# level_shifter.net
KiCad netlist of a schematic drawn in Altium Designer
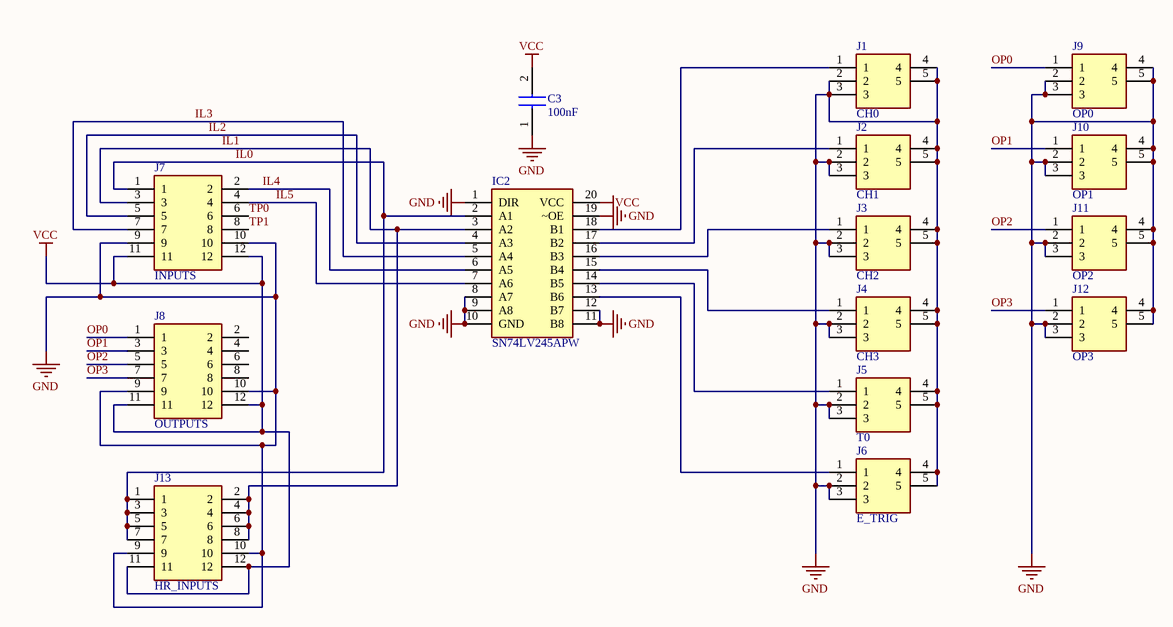
[diagram p0: level_shifter.SchDoc]

(export (version "E")
  (design (tool "Eeschema 10.0.6"))
  (components
    (comp (ref "C3")
      (value "100nF")
      (footprint "SamacSys:CAPC1005X56N")
      (description "Capacitor")
      (fields
        (field (name "MANUFACTURER_PART_NUMBER") "0402YC104MAT2A")
        (field (name "MOUSER PART NUMBER") "581-0402YC104MAT2A")
      )
      (libsource (lib "*") (part "0402YC104MAT2A"))
    )
    (comp (ref "IC2")
      (value "SN74LV245APW")
      (footprint "SamacSys:SOP65P640X120-20N")
      (description "Integrated Circuit")
      (fields
        (field (name "MOUSER PART NUMBER") "595-SN74LV245APW")
        (field (name "RS PART NUMBER") "4394371")
      )
      (libsource (lib "*") (part "SN74LV245APW"))
    )
    (comp (ref "J1")
      (value "CH0")
      (footprint "SamacSys:142-0701-501")
      (description "Connector")
      (fields
        (field (name "RS PART NUMBER") "8859850")
        (field (name "MANUFACTURER_PART_NUMBER") "142-0701-501")
      )
      (libsource (lib "*") (part "142-0701-501"))
    )
    (comp (ref "J2")
      (value "CH1")
      (footprint "SamacSys:142-0701-501")
      (description "Connector")
      (fields
        (field (name "RS PART NUMBER") "8859850")
        (field (name "MANUFACTURER_PART_NUMBER") "142-0701-501")
      )
      (libsource (lib "*") (part "142-0701-501"))
    )
    (comp (ref "J3")
      (value "CH2")
      (footprint "SamacSys:142-0701-501")
      (description "Connector")
      (fields
        (field (name "RS PART NUMBER") "8859850")
        (field (name "MANUFACTURER_PART_NUMBER") "142-0701-501")
      )
      (libsource (lib "*") (part "142-0701-501"))
    )
    (comp (ref "J4")
      (value "CH3")
      (footprint "SamacSys:142-0701-501")
      (description "Connector")
      (fields
        (field (name "RS PART NUMBER") "8859850")
        (field (name "MANUFACTURER_PART_NUMBER") "142-0701-501")
      )
      (libsource (lib "*") (part "142-0701-501"))
    )
    (comp (ref "J5")
      (value "T0")
      (footprint "SamacSys:142-0701-501")
      (description "Connector")
      (fields
        (field (name "RS PART NUMBER") "8859850")
        (field (name "MANUFACTURER_PART_NUMBER") "142-0701-501")
      )
      (libsource (lib "*") (part "142-0701-501"))
    )
    (comp (ref "J6")
      (value "E_TRIG")
      (footprint "SamacSys:142-0701-501")
      (description "Connector")
      (fields
        (field (name "RS PART NUMBER") "8859850")
        (field (name "MANUFACTURER_PART_NUMBER") "142-0701-501")
      )
      (libsource (lib "*") (part "142-0701-501"))
    )
    (comp (ref "J7")
      (value "INPUTS")
      (footprint "SamacSys:HDRRA12W64P254_2X6_1524X254X610P")
      (description "Connector")
      (fields
        (field (name "MANUFACTURER_PART_NUMBER") "TSW-106-08-L-D-RA")
        (field (name "MOUSER PART NUMBER") "200-TSW10608LDRA")
      )
      (libsource (lib "*") (part "TSW-106-08-L-D-RA"))
    )
    (comp (ref "J8")
      (value "OUTPUTS")
      (footprint "SamacSys:HDRRA12W64P254_2X6_1524X254X610P")
      (description "Connector")
      (fields
        (field (name "MANUFACTURER_PART_NUMBER") "TSW-106-08-L-D-RA")
        (field (name "MOUSER PART NUMBER") "200-TSW10608LDRA")
      )
      (libsource (lib "*") (part "TSW-106-08-L-D-RA"))
    )
    (comp (ref "J9")
      (value "OP0")
      (footprint "SamacSys:142-0701-501")
      (description "Connector")
      (fields
        (field (name "RS PART NUMBER") "8859850")
        (field (name "MANUFACTURER_PART_NUMBER") "142-0701-501")
      )
      (libsource (lib "*") (part "142-0701-501"))
    )
    (comp (ref "J10")
      (value "OP1")
      (footprint "SamacSys:142-0701-501")
      (description "Connector")
      (fields
        (field (name "RS PART NUMBER") "8859850")
        (field (name "MANUFACTURER_PART_NUMBER") "142-0701-501")
      )
      (libsource (lib "*") (part "142-0701-501"))
    )
    (comp (ref "J11")
      (value "OP2")
      (footprint "SamacSys:142-0701-501")
      (description "Connector")
      (fields
        (field (name "RS PART NUMBER") "8859850")
        (field (name "MANUFACTURER_PART_NUMBER") "142-0701-501")
      )
      (libsource (lib "*") (part "142-0701-501"))
    )
    (comp (ref "J12")
      (value "OP3")
      (footprint "SamacSys:142-0701-501")
      (description "Connector")
      (fields
        (field (name "RS PART NUMBER") "8859850")
        (field (name "MANUFACTURER_PART_NUMBER") "142-0701-501")
      )
      (libsource (lib "*") (part "142-0701-501"))
    )
    (comp (ref "J13")
      (value "HR_INPUTS")
      (footprint "SamacSys:HDRRA12W64P254_2X6_1524X254X610P")
      (description "Connector")
      (fields
        (field (name "MANUFACTURER_PART_NUMBER") "TSW-106-08-L-D-RA")
        (field (name "MOUSER PART NUMBER") "200-TSW10608LDRA")
      )
      (libsource (lib "*") (part "TSW-106-08-L-D-RA"))
    )
  )
  (nets
    (net (code "1") (name "/IL0") (class "Default")
      (node (ref "IC2") (pin "2") (pinfunction "A1_2") (pintype "passive"))
      (node (ref "J13") (pin "1") (pinfunction "1_1") (pintype "passive"))
      (node (ref "J13") (pin "3") (pinfunction "3_3") (pintype "passive"))
      (node (ref "J13") (pin "5") (pinfunction "5_5") (pintype "passive"))
      (node (ref "J13") (pin "7") (pinfunction "7_7") (pintype "passive"))
      (node (ref "J7") (pin "1") (pinfunction "1_1") (pintype "passive"))
    )
    (net (code "2") (name "/IL1") (class "Default")
      (node (ref "IC2") (pin "3") (pinfunction "A2_3") (pintype "passive"))
      (node (ref "J13") (pin "2") (pinfunction "2_2") (pintype "passive"))
      (node (ref "J13") (pin "4") (pinfunction "4_4") (pintype "passive"))
      (node (ref "J13") (pin "6") (pinfunction "6_6") (pintype "passive"))
      (node (ref "J13") (pin "8") (pinfunction "8_8") (pintype "passive"))
      (node (ref "J7") (pin "3") (pinfunction "3_3") (pintype "passive"))
    )
    (net (code "3") (name "/IL2") (class "Default")
      (node (ref "IC2") (pin "4") (pinfunction "A3_4") (pintype "passive"))
      (node (ref "J7") (pin "5") (pinfunction "5_5") (pintype "passive"))
    )
    (net (code "4") (name "/IL3") (class "Default")
      (node (ref "IC2") (pin "5") (pinfunction "A4_5") (pintype "passive"))
      (node (ref "J7") (pin "7") (pinfunction "7_7") (pintype "passive"))
    )
    (net (code "5") (name "/IL4") (class "Default")
      (node (ref "IC2") (pin "6") (pinfunction "A5_6") (pintype "passive"))
      (node (ref "J7") (pin "2") (pinfunction "2_2") (pintype "passive"))
    )
    (net (code "6") (name "/IL5") (class "Default")
      (node (ref "IC2") (pin "7") (pinfunction "A6_7") (pintype "passive"))
      (node (ref "J7") (pin "4") (pinfunction "4_4") (pintype "passive"))
    )
    (net (code "7") (name "/OP0") (class "Default")
      (node (ref "J8") (pin "1") (pinfunction "1_1") (pintype "passive"))
      (node (ref "J9") (pin "1") (pinfunction "1_1") (pintype "passive"))
    )
    (net (code "8") (name "/OP1") (class "Default")
      (node (ref "J10") (pin "1") (pinfunction "1_1") (pintype "passive"))
      (node (ref "J8") (pin "3") (pinfunction "3_3") (pintype "passive"))
    )
    (net (code "9") (name "/OP2") (class "Default")
      (node (ref "J11") (pin "1") (pinfunction "1_1") (pintype "passive"))
      (node (ref "J8") (pin "5") (pinfunction "5_5") (pintype "passive"))
    )
    (net (code "10") (name "/OP3") (class "Default")
      (node (ref "J12") (pin "1") (pinfunction "1_1") (pintype "passive"))
      (node (ref "J8") (pin "7") (pinfunction "7_7") (pintype "passive"))
    )
    (net (code "11") (name "/TP0") (class "Default")
      (node (ref "J7") (pin "6") (pinfunction "6_6") (pintype "passive"))
    )
    (net (code "12") (name "/TP1") (class "Default")
      (node (ref "J7") (pin "8") (pinfunction "8_8") (pintype "passive"))
    )
    (net (code "13") (name "GND") (class "Default")
      (node (ref "C3") (pin "1") (pinfunction "1_1") (pintype "passive"))
      (node (ref "IC2") (pin "1") (pinfunction "DIR_1") (pintype "passive"))
      (node (ref "IC2") (pin "10") (pinfunction "GND_10") (pintype "passive"))
      (node (ref "IC2") (pin "11") (pinfunction "B8_11") (pintype "passive"))
      (node (ref "IC2") (pin "12") (pinfunction "B7_12") (pintype "passive"))
      (node (ref "IC2") (pin "19") (pinfunction "~OE_19") (pintype "passive"))
      (node (ref "IC2") (pin "8") (pinfunction "A7_8") (pintype "passive"))
      (node (ref "IC2") (pin "9") (pinfunction "A8_9") (pintype "passive"))
      (node (ref "J1") (pin "2") (pinfunction "2_2") (pintype "passive"))
      (node (ref "J1") (pin "3") (pinfunction "3_3") (pintype "passive"))
      (node (ref "J1") (pin "4") (pinfunction "4_4") (pintype "passive"))
      (node (ref "J1") (pin "5") (pinfunction "5_5") (pintype "passive"))
      (node (ref "J10") (pin "2") (pinfunction "2_2") (pintype "passive"))
      (node (ref "J10") (pin "3") (pinfunction "3_3") (pintype "passive"))
      (node (ref "J10") (pin "4") (pinfunction "4_4") (pintype "passive"))
      (node (ref "J10") (pin "5") (pinfunction "5_5") (pintype "passive"))
      (node (ref "J11") (pin "2") (pinfunction "2_2") (pintype "passive"))
      (node (ref "J11") (pin "3") (pinfunction "3_3") (pintype "passive"))
      (node (ref "J11") (pin "4") (pinfunction "4_4") (pintype "passive"))
      (node (ref "J11") (pin "5") (pinfunction "5_5") (pintype "passive"))
      (node (ref "J12") (pin "2") (pinfunction "2_2") (pintype "passive"))
      (node (ref "J12") (pin "3") (pinfunction "3_3") (pintype "passive"))
      (node (ref "J12") (pin "4") (pinfunction "4_4") (pintype "passive"))
      (node (ref "J12") (pin "5") (pinfunction "5_5") (pintype "passive"))
      (node (ref "J13") (pin "10") (pinfunction "10_10") (pintype "passive"))
      (node (ref "J13") (pin "9") (pinfunction "9_9") (pintype "passive"))
      (node (ref "J2") (pin "2") (pinfunction "2_2") (pintype "passive"))
      (node (ref "J2") (pin "3") (pinfunction "3_3") (pintype "passive"))
      (node (ref "J2") (pin "4") (pinfunction "4_4") (pintype "passive"))
      (node (ref "J2") (pin "5") (pinfunction "5_5") (pintype "passive"))
      (node (ref "J3") (pin "2") (pinfunction "2_2") (pintype "passive"))
      (node (ref "J3") (pin "3") (pinfunction "3_3") (pintype "passive"))
      (node (ref "J3") (pin "4") (pinfunction "4_4") (pintype "passive"))
      (node (ref "J3") (pin "5") (pinfunction "5_5") (pintype "passive"))
      (node (ref "J4") (pin "2") (pinfunction "2_2") (pintype "passive"))
      (node (ref "J4") (pin "3") (pinfunction "3_3") (pintype "passive"))
      (node (ref "J4") (pin "4") (pinfunction "4_4") (pintype "passive"))
      (node (ref "J4") (pin "5") (pinfunction "5_5") (pintype "passive"))
      (node (ref "J5") (pin "2") (pinfunction "2_2") (pintype "passive"))
      (node (ref "J5") (pin "3") (pinfunction "3_3") (pintype "passive"))
      (node (ref "J5") (pin "4") (pinfunction "4_4") (pintype "passive"))
      (node (ref "J5") (pin "5") (pinfunction "5_5") (pintype "passive"))
      (node (ref "J6") (pin "2") (pinfunction "2_2") (pintype "passive"))
      (node (ref "J6") (pin "3") (pinfunction "3_3") (pintype "passive"))
      (node (ref "J6") (pin "4") (pinfunction "4_4") (pintype "passive"))
      (node (ref "J6") (pin "5") (pinfunction "5_5") (pintype "passive"))
      (node (ref "J7") (pin "10") (pinfunction "10_10") (pintype "passive"))
      (node (ref "J7") (pin "9") (pinfunction "9_9") (pintype "passive"))
      (node (ref "J8") (pin "10") (pinfunction "10_10") (pintype "passive"))
      (node (ref "J8") (pin "9") (pinfunction "9_9") (pintype "passive"))
      (node (ref "J9") (pin "2") (pinfunction "2_2") (pintype "passive"))
      (node (ref "J9") (pin "3") (pinfunction "3_3") (pintype "passive"))
      (node (ref "J9") (pin "4") (pinfunction "4_4") (pintype "passive"))
      (node (ref "J9") (pin "5") (pinfunction "5_5") (pintype "passive"))
    )
    (net (code "14") (name "Net-(IC2-B1)") (class "Default")
      (node (ref "IC2") (pin "18") (pinfunction "B1_18") (pintype "passive"))
      (node (ref "J1") (pin "1") (pinfunction "1_1") (pintype "passive"))
    )
    (net (code "15") (name "Net-(IC2-B2)") (class "Default")
      (node (ref "IC2") (pin "17") (pinfunction "B2_17") (pintype "passive"))
      (node (ref "J2") (pin "1") (pinfunction "1_1") (pintype "passive"))
    )
    (net (code "16") (name "Net-(IC2-B3)") (class "Default")
      (node (ref "IC2") (pin "16") (pinfunction "B3_16") (pintype "passive"))
      (node (ref "J3") (pin "1") (pinfunction "1_1") (pintype "passive"))
    )
    (net (code "17") (name "Net-(IC2-B4)") (class "Default")
      (node (ref "IC2") (pin "15") (pinfunction "B4_15") (pintype "passive"))
      (node (ref "J4") (pin "1") (pinfunction "1_1") (pintype "passive"))
    )
    (net (code "18") (name "Net-(IC2-B5)") (class "Default")
      (node (ref "IC2") (pin "14") (pinfunction "B5_14") (pintype "passive"))
      (node (ref "J5") (pin "1") (pinfunction "1_1") (pintype "passive"))
    )
    (net (code "19") (name "Net-(IC2-B6)") (class "Default")
      (node (ref "IC2") (pin "13") (pinfunction "B6_13") (pintype "passive"))
      (node (ref "J6") (pin "1") (pinfunction "1_1") (pintype "passive"))
    )
    (net (code "20") (name "VCC") (class "Default")
      (node (ref "C3") (pin "2") (pinfunction "2_2") (pintype "passive"))
      (node (ref "IC2") (pin "20") (pinfunction "VCC_20") (pintype "passive"))
      (node (ref "J13") (pin "11") (pinfunction "11_11") (pintype "passive"))
      (node (ref "J13") (pin "12") (pinfunction "12_12") (pintype "passive"))
      (node (ref "J7") (pin "11") (pinfunction "11_11") (pintype "passive"))
      (node (ref "J7") (pin "12") (pinfunction "12_12") (pintype "passive"))
      (node (ref "J8") (pin "11") (pinfunction "11_11") (pintype "passive"))
      (node (ref "J8") (pin "12") (pinfunction "12_12") (pintype "passive"))
    )
    (net (code "21") (name "unconnected-(J8-Pad2)") (class "Default")
      (node (ref "J8") (pin "2") (pinfunction "2_2") (pintype "passive"))
    )
    (net (code "22") (name "unconnected-(J8-Pad4)") (class "Default")
      (node (ref "J8") (pin "4") (pinfunction "4_4") (pintype "passive"))
    )
    (net (code "23") (name "unconnected-(J8-Pad6)") (class "Default")
      (node (ref "J8") (pin "6") (pinfunction "6_6") (pintype "passive"))
    )
    (net (code "24") (name "unconnected-(J8-Pad8)") (class "Default")
      (node (ref "J8") (pin "8") (pinfunction "8_8") (pintype "passive"))
    )
  )
)
